# Blinky_Trevor.net
KiCad netlist of a schematic drawn in EAGLE
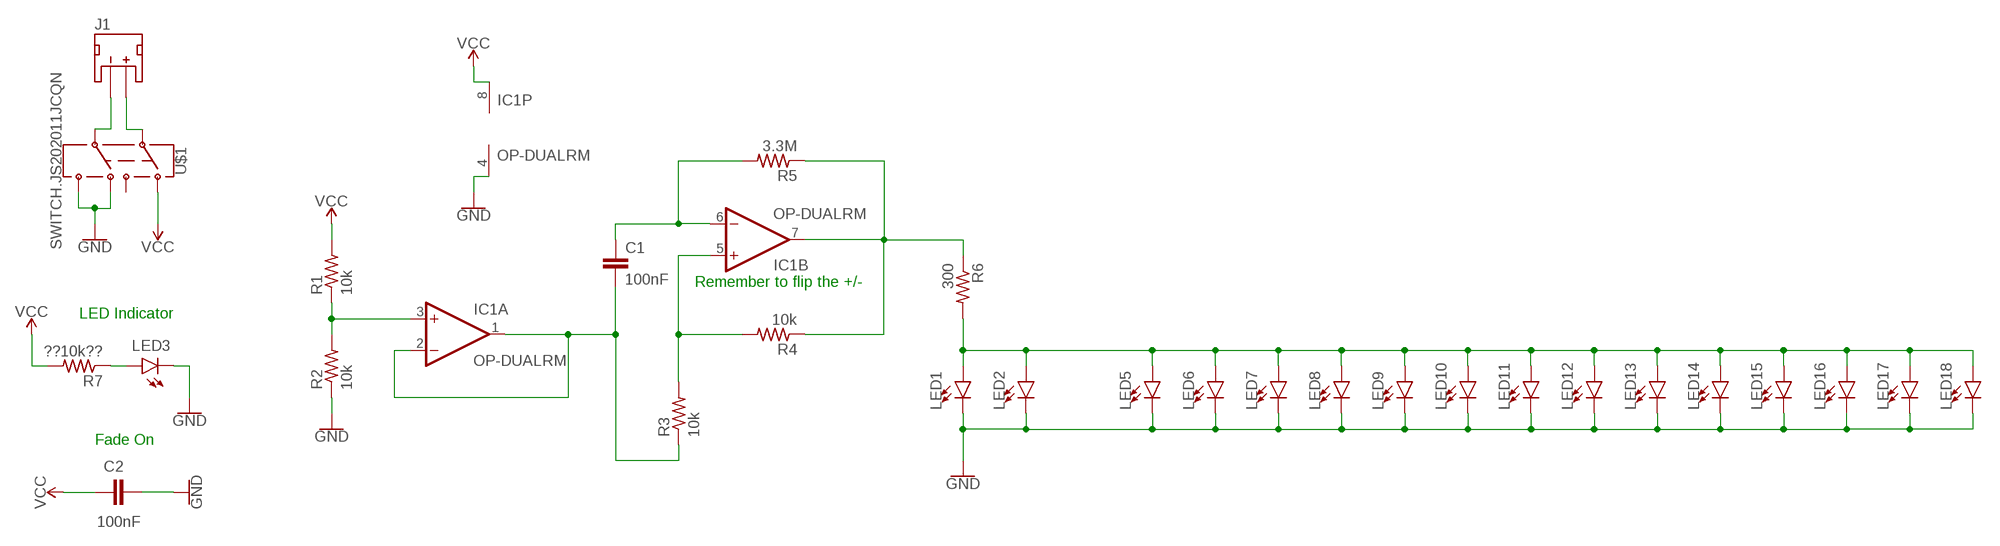
[diagram p0: schematic, sheet 1]

(export (version "E")
  (design (tool "Eeschema 10.0.6"))
  (components
    (comp (ref "C1")
      (value "100nF")
      (footprint "eagle-import:C0402")
      (libsource (lib "eagle-import") (part "CAPACITOR0402"))
    )
    (comp (ref "C2")
      (value "100nF")
      (footprint "eagle-import:C0402")
      (libsource (lib "eagle-import") (part "CAPACITOR0402"))
    )
    (comp (ref "IC1")
      (value "OP-DUALRM")
      (footprint "eagle-import:MSOP08")
      (fields (field (name "MF") "ALTERA CORPORATION") (field (name "MPN") "AD8607ARMZ-REEL"))
      (libsource (lib "eagle-import") (part "OP-DUALRM"))
    )
    (comp (ref "J1")
      (value "JST_2MM_MALE")
      (footprint "eagle-import:JST-2-SMD")
      (libsource (lib "eagle-import") (part "JST_2MM_MALE"))
    )
    (comp (ref "LED1")
      (value "LED0603")
      (footprint "eagle-import:LED-0603")
      (libsource (lib "eagle-import") (part "LED0603"))
    )
    (comp (ref "LED2")
      (value "LED0603")
      (footprint "eagle-import:LED-0603")
      (libsource (lib "eagle-import") (part "LED0603"))
    )
    (comp (ref "LED3")
      (value "LED0603")
      (footprint "eagle-import:LED-0603")
      (libsource (lib "eagle-import") (part "LED0603"))
    )
    (comp (ref "LED5")
      (value "LED0603")
      (footprint "eagle-import:LED-0603")
      (libsource (lib "eagle-import") (part "LED0603"))
    )
    (comp (ref "LED6")
      (value "LED0603")
      (footprint "eagle-import:LED-0603")
      (libsource (lib "eagle-import") (part "LED0603"))
    )
    (comp (ref "LED7")
      (value "LED0603")
      (footprint "eagle-import:LED-0603")
      (libsource (lib "eagle-import") (part "LED0603"))
    )
    (comp (ref "LED8")
      (value "LED0603")
      (footprint "eagle-import:LED-0603")
      (libsource (lib "eagle-import") (part "LED0603"))
    )
    (comp (ref "LED9")
      (value "LED0603")
      (footprint "eagle-import:LED-0603")
      (libsource (lib "eagle-import") (part "LED0603"))
    )
    (comp (ref "LED10")
      (value "LED0603")
      (footprint "eagle-import:LED-0603")
      (libsource (lib "eagle-import") (part "LED0603"))
    )
    (comp (ref "LED11")
      (value "LED0603")
      (footprint "eagle-import:LED-0603")
      (libsource (lib "eagle-import") (part "LED0603"))
    )
    (comp (ref "LED12")
      (value "LED0603")
      (footprint "eagle-import:LED-0603")
      (libsource (lib "eagle-import") (part "LED0603"))
    )
    (comp (ref "LED13")
      (value "LED0603")
      (footprint "eagle-import:LED-0603")
      (libsource (lib "eagle-import") (part "LED0603"))
    )
    (comp (ref "LED14")
      (value "LED0603")
      (footprint "eagle-import:LED-0603")
      (libsource (lib "eagle-import") (part "LED0603"))
    )
    (comp (ref "LED15")
      (value "LED0603")
      (footprint "eagle-import:LED-0603")
      (libsource (lib "eagle-import") (part "LED0603"))
    )
    (comp (ref "LED16")
      (value "LED0603")
      (footprint "eagle-import:LED-0603")
      (libsource (lib "eagle-import") (part "LED0603"))
    )
    (comp (ref "LED17")
      (value "LED0603")
      (footprint "eagle-import:LED-0603")
      (libsource (lib "eagle-import") (part "LED0603"))
    )
    (comp (ref "LED18")
      (value "LED0603")
      (footprint "eagle-import:LED-0603")
      (libsource (lib "eagle-import") (part "LED0603"))
    )
    (comp (ref "R1")
      (value "10k")
      (footprint "eagle-import:R0402")
      (libsource (lib "eagle-import") (part "RESISTOR0402"))
    )
    (comp (ref "R2")
      (value "10k")
      (footprint "eagle-import:R0402")
      (libsource (lib "eagle-import") (part "RESISTOR0402"))
    )
    (comp (ref "R3")
      (value "10k")
      (footprint "eagle-import:R0402")
      (libsource (lib "eagle-import") (part "RESISTOR0402"))
    )
    (comp (ref "R4")
      (value "10k")
      (footprint "eagle-import:R0402")
      (libsource (lib "eagle-import") (part "RESISTOR0402"))
    )
    (comp (ref "R5")
      (value "3.3M")
      (footprint "eagle-import:R0402")
      (libsource (lib "eagle-import") (part "RESISTOR0402"))
    )
    (comp (ref "R6")
      (value "300")
      (footprint "eagle-import:R0402")
      (libsource (lib "eagle-import") (part "RESISTOR0402"))
    )
    (comp (ref "R7")
      (value "??10k??")
      (footprint "eagle-import:R0402")
      (libsource (lib "eagle-import") (part "RESISTOR0402"))
    )
    (comp (ref "U$1")
      (value "SWITCH.JS202011JCQN")
      (footprint "eagle-import:SWITCH.00")
      (libsource (lib "eagle-import") (part "SWITCH.JS202011JCQN"))
    )
  )
  (nets
    (net (code "1") (name "GND") (class "Default")
      (node (ref "C2") (pin "2") (pinfunction "2_2") (pintype "passive"))
      (node (ref "IC1") (pin "4") (pinfunction "V-_4") (pintype "power_in"))
      (node (ref "LED1") (pin "C") (pinfunction "C_C") (pintype "passive"))
      (node (ref "LED10") (pin "C") (pinfunction "C_C") (pintype "passive"))
      (node (ref "LED11") (pin "C") (pinfunction "C_C") (pintype "passive"))
      (node (ref "LED12") (pin "C") (pinfunction "C_C") (pintype "passive"))
      (node (ref "LED13") (pin "C") (pinfunction "C_C") (pintype "passive"))
      (node (ref "LED14") (pin "C") (pinfunction "C_C") (pintype "passive"))
      (node (ref "LED15") (pin "C") (pinfunction "C_C") (pintype "passive"))
      (node (ref "LED16") (pin "C") (pinfunction "C_C") (pintype "passive"))
      (node (ref "LED17") (pin "C") (pinfunction "C_C") (pintype "passive"))
      (node (ref "LED18") (pin "C") (pinfunction "C_C") (pintype "passive"))
      (node (ref "LED2") (pin "C") (pinfunction "C_C") (pintype "passive"))
      (node (ref "LED3") (pin "C") (pinfunction "C_C") (pintype "passive"))
      (node (ref "LED5") (pin "C") (pinfunction "C_C") (pintype "passive"))
      (node (ref "LED6") (pin "C") (pinfunction "C_C") (pintype "passive"))
      (node (ref "LED7") (pin "C") (pinfunction "C_C") (pintype "passive"))
      (node (ref "LED8") (pin "C") (pinfunction "C_C") (pintype "passive"))
      (node (ref "LED9") (pin "C") (pinfunction "C_C") (pintype "passive"))
      (node (ref "R2") (pin "1") (pinfunction "1_1") (pintype "passive"))
      (node (ref "U$1") (pin "5") (pinfunction "5_5") (pintype "bidirectional"))
      (node (ref "U$1") (pin "7") (pinfunction "7_7") (pintype "bidirectional"))
    )
    (net (code "2") (name "Net-(IC1A-+IN)") (class "Default")
      (node (ref "IC1") (pin "3") (pinfunction "+IN_3") (pintype "input"))
      (node (ref "R1") (pin "1") (pinfunction "1_1") (pintype "passive"))
      (node (ref "R2") (pin "2") (pinfunction "2_2") (pintype "passive"))
    )
    (net (code "3") (name "Net-(IC1A--IN)") (class "Default")
      (node (ref "C1") (pin "2") (pinfunction "2_2") (pintype "passive"))
      (node (ref "IC1") (pin "1") (pinfunction "OUT_1") (pintype "output"))
      (node (ref "IC1") (pin "2") (pinfunction "-IN_2") (pintype "input"))
      (node (ref "R3") (pin "1") (pinfunction "1_1") (pintype "passive"))
    )
    (net (code "4") (name "Net-(IC1B-+IN)") (class "Default")
      (node (ref "IC1") (pin "5") (pinfunction "+IN_5") (pintype "input"))
      (node (ref "R3") (pin "2") (pinfunction "2_2") (pintype "passive"))
      (node (ref "R4") (pin "2") (pinfunction "2_2") (pintype "passive"))
    )
    (net (code "5") (name "Net-(IC1B--IN)") (class "Default")
      (node (ref "C1") (pin "1") (pinfunction "1_1") (pintype "passive"))
      (node (ref "IC1") (pin "6") (pinfunction "-IN_6") (pintype "input"))
      (node (ref "R5") (pin "2") (pinfunction "2_2") (pintype "passive"))
    )
    (net (code "6") (name "Net-(IC1B-OUT)") (class "Default")
      (node (ref "IC1") (pin "7") (pinfunction "OUT_7") (pintype "output"))
      (node (ref "R4") (pin "1") (pinfunction "1_1") (pintype "passive"))
      (node (ref "R5") (pin "1") (pinfunction "1_1") (pintype "passive"))
      (node (ref "R6") (pin "1") (pinfunction "1_1") (pintype "passive"))
    )
    (net (code "7") (name "Net-(J1-+)") (class "Default")
      (node (ref "J1") (pin "2") (pinfunction "+_2") (pintype "bidirectional"))
      (node (ref "U$1") (pin "2") (pinfunction "2_2") (pintype "bidirectional"))
    )
    (net (code "8") (name "Net-(J1--)") (class "Default")
      (node (ref "J1") (pin "1") (pinfunction "-_1") (pintype "bidirectional"))
      (node (ref "U$1") (pin "6") (pinfunction "6_6") (pintype "bidirectional"))
    )
    (net (code "9") (name "Net-(LED1-PadA)") (class "Default")
      (node (ref "LED1") (pin "A") (pinfunction "A_A") (pintype "passive"))
      (node (ref "LED10") (pin "A") (pinfunction "A_A") (pintype "passive"))
      (node (ref "LED11") (pin "A") (pinfunction "A_A") (pintype "passive"))
      (node (ref "LED12") (pin "A") (pinfunction "A_A") (pintype "passive"))
      (node (ref "LED13") (pin "A") (pinfunction "A_A") (pintype "passive"))
      (node (ref "LED14") (pin "A") (pinfunction "A_A") (pintype "passive"))
      (node (ref "LED15") (pin "A") (pinfunction "A_A") (pintype "passive"))
      (node (ref "LED16") (pin "A") (pinfunction "A_A") (pintype "passive"))
      (node (ref "LED17") (pin "A") (pinfunction "A_A") (pintype "passive"))
      (node (ref "LED18") (pin "A") (pinfunction "A_A") (pintype "passive"))
      (node (ref "LED2") (pin "A") (pinfunction "A_A") (pintype "passive"))
      (node (ref "LED5") (pin "A") (pinfunction "A_A") (pintype "passive"))
      (node (ref "LED6") (pin "A") (pinfunction "A_A") (pintype "passive"))
      (node (ref "LED7") (pin "A") (pinfunction "A_A") (pintype "passive"))
      (node (ref "LED8") (pin "A") (pinfunction "A_A") (pintype "passive"))
      (node (ref "LED9") (pin "A") (pinfunction "A_A") (pintype "passive"))
      (node (ref "R6") (pin "2") (pinfunction "2_2") (pintype "passive"))
    )
    (net (code "10") (name "Net-(LED3-PadA)") (class "Default")
      (node (ref "LED3") (pin "A") (pinfunction "A_A") (pintype "passive"))
      (node (ref "R7") (pin "1") (pinfunction "1_1") (pintype "passive"))
    )
    (net (code "11") (name "VCC") (class "Default")
      (node (ref "C2") (pin "1") (pinfunction "1_1") (pintype "passive"))
      (node (ref "IC1") (pin "8") (pinfunction "V+_8") (pintype "power_in"))
      (node (ref "R1") (pin "2") (pinfunction "2_2") (pintype "passive"))
      (node (ref "R7") (pin "2") (pinfunction "2_2") (pintype "passive"))
      (node (ref "U$1") (pin "1") (pinfunction "1_1") (pintype "bidirectional"))
    )
    (net (code "12") (name "unconnected-(J1-PAD1-PadNC1)") (class "Default")
      (node (ref "J1") (pin "NC1") (pinfunction "PAD1_NC1") (pintype "bidirectional"))
    )
    (net (code "13") (name "unconnected-(J1-PAD2-PadNC2)") (class "Default")
      (node (ref "J1") (pin "NC2") (pinfunction "PAD2_NC2") (pintype "bidirectional"))
    )
    (net (code "14") (name "unconnected-(U$1-Pad3)") (class "Default")
      (node (ref "U$1") (pin "3") (pinfunction "3_3") (pintype "bidirectional"))
    )
  )
)
